# MTB-v2_0_0.net
KiCad netlist of a schematic drawn in EAGLE
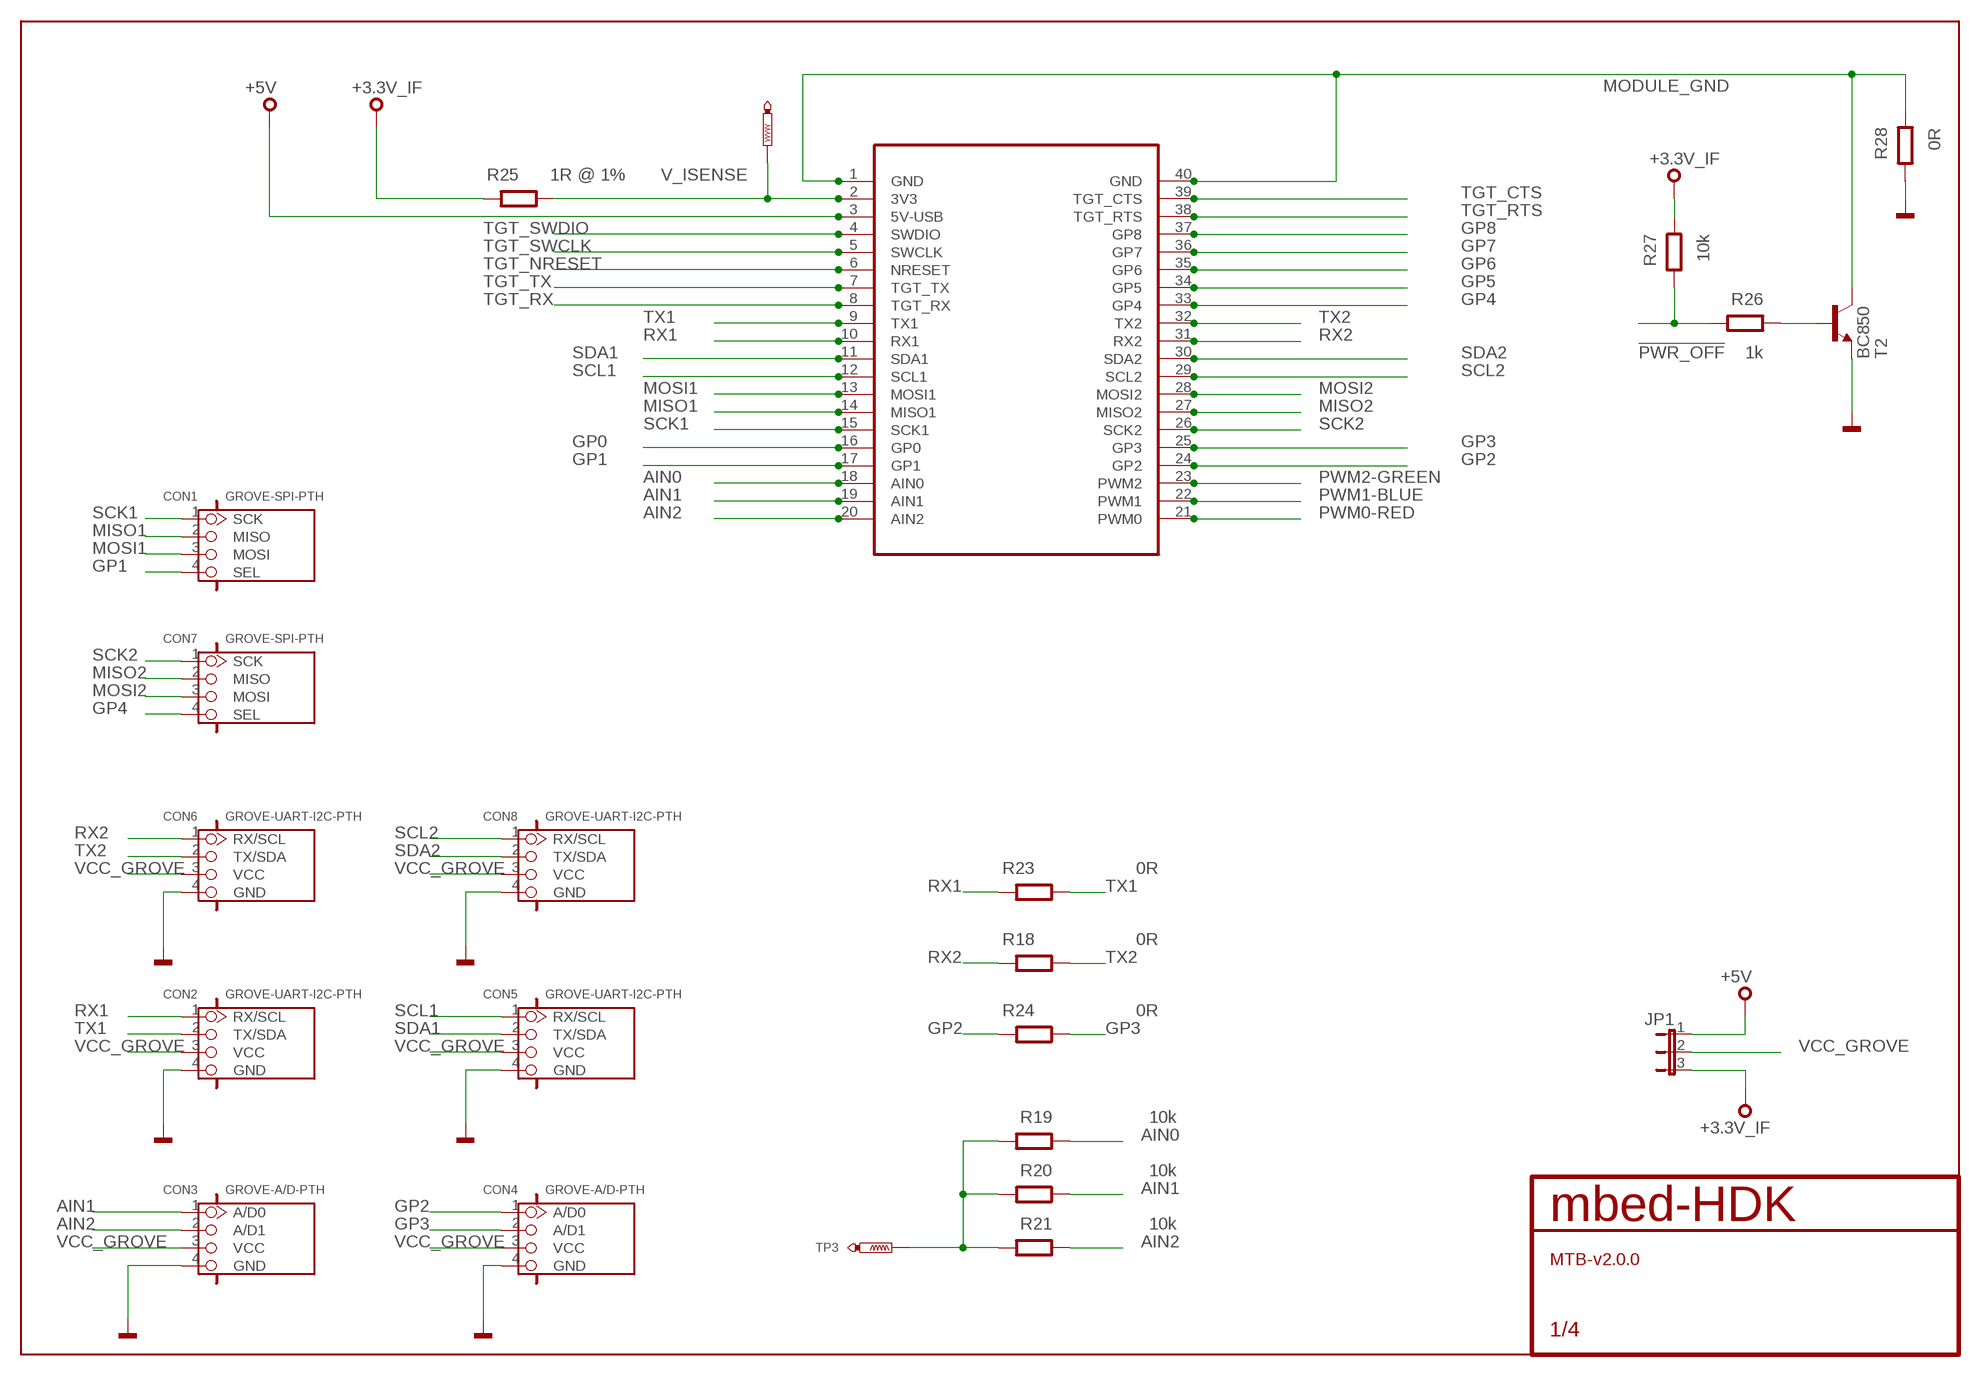
[diagram p0: schematic, sheet 1]
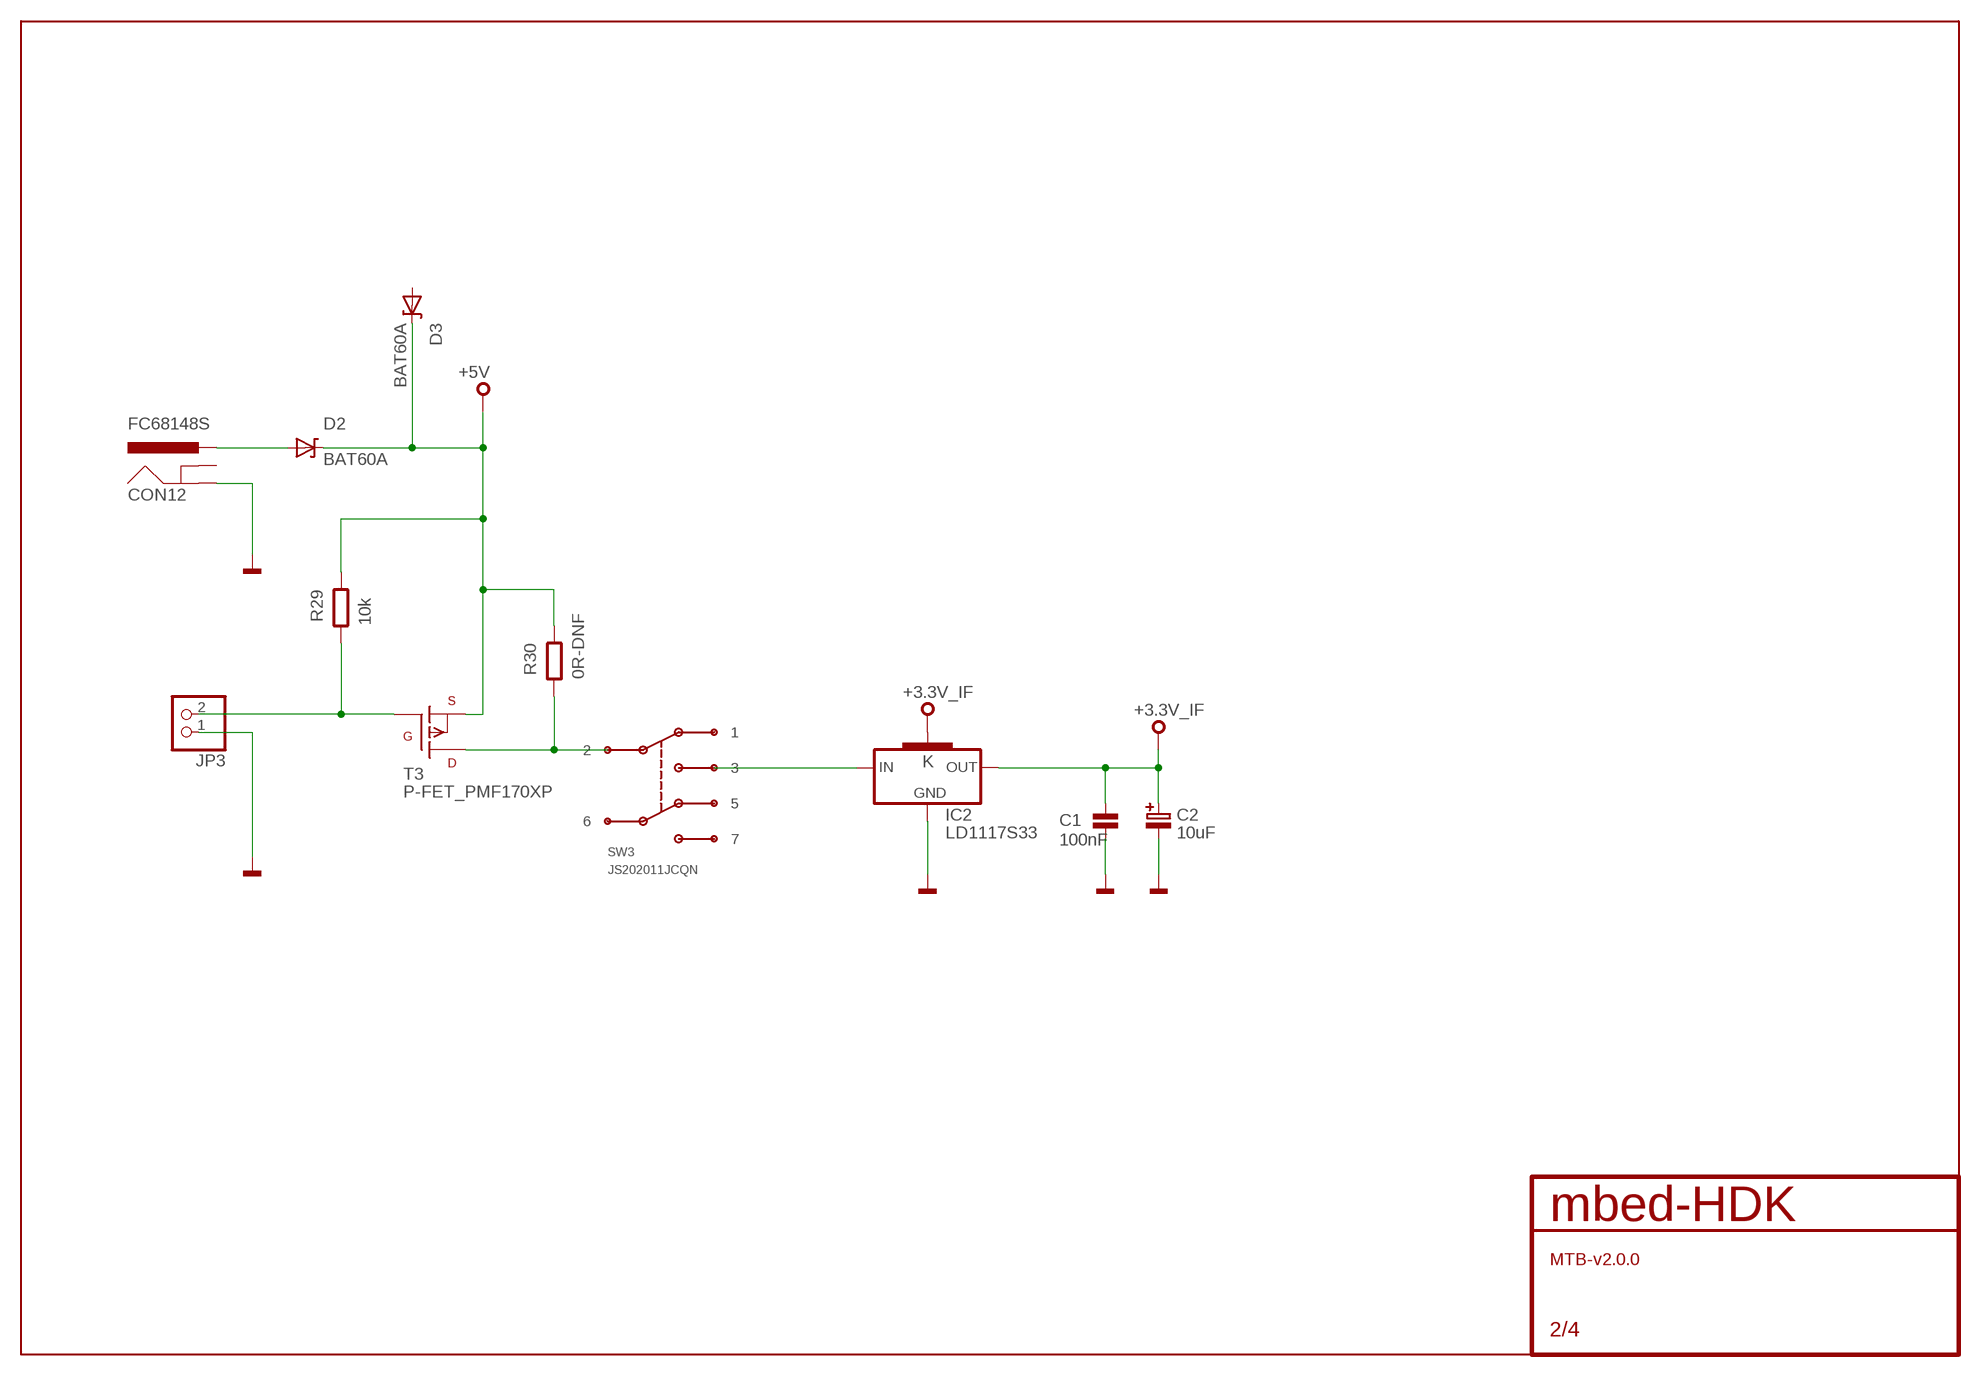
[diagram p1: schematic, sheet 2]
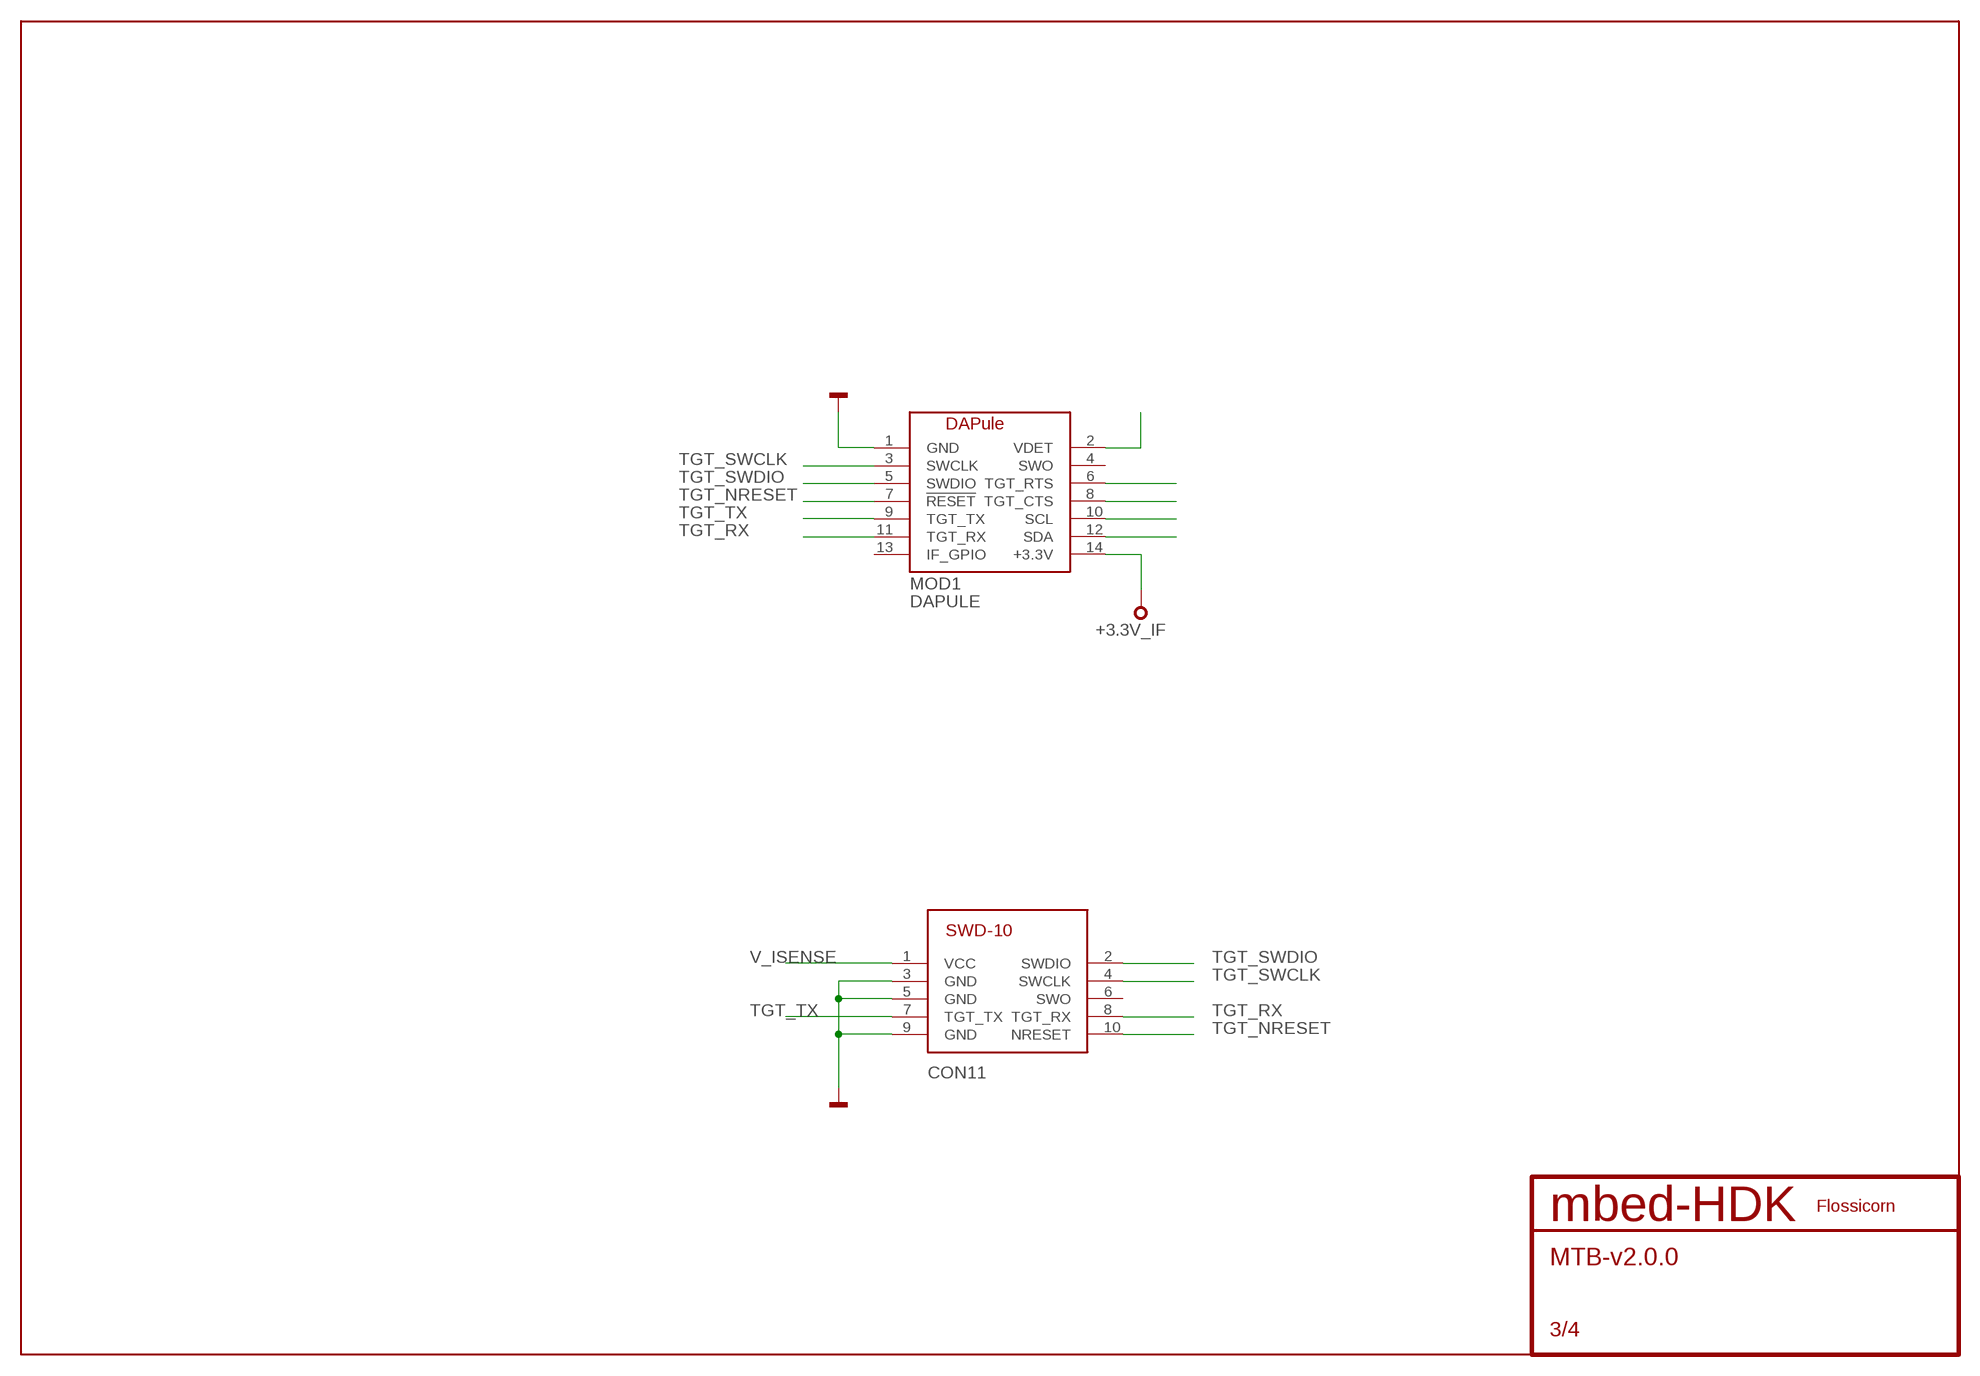
[diagram p2: schematic, sheet 3]
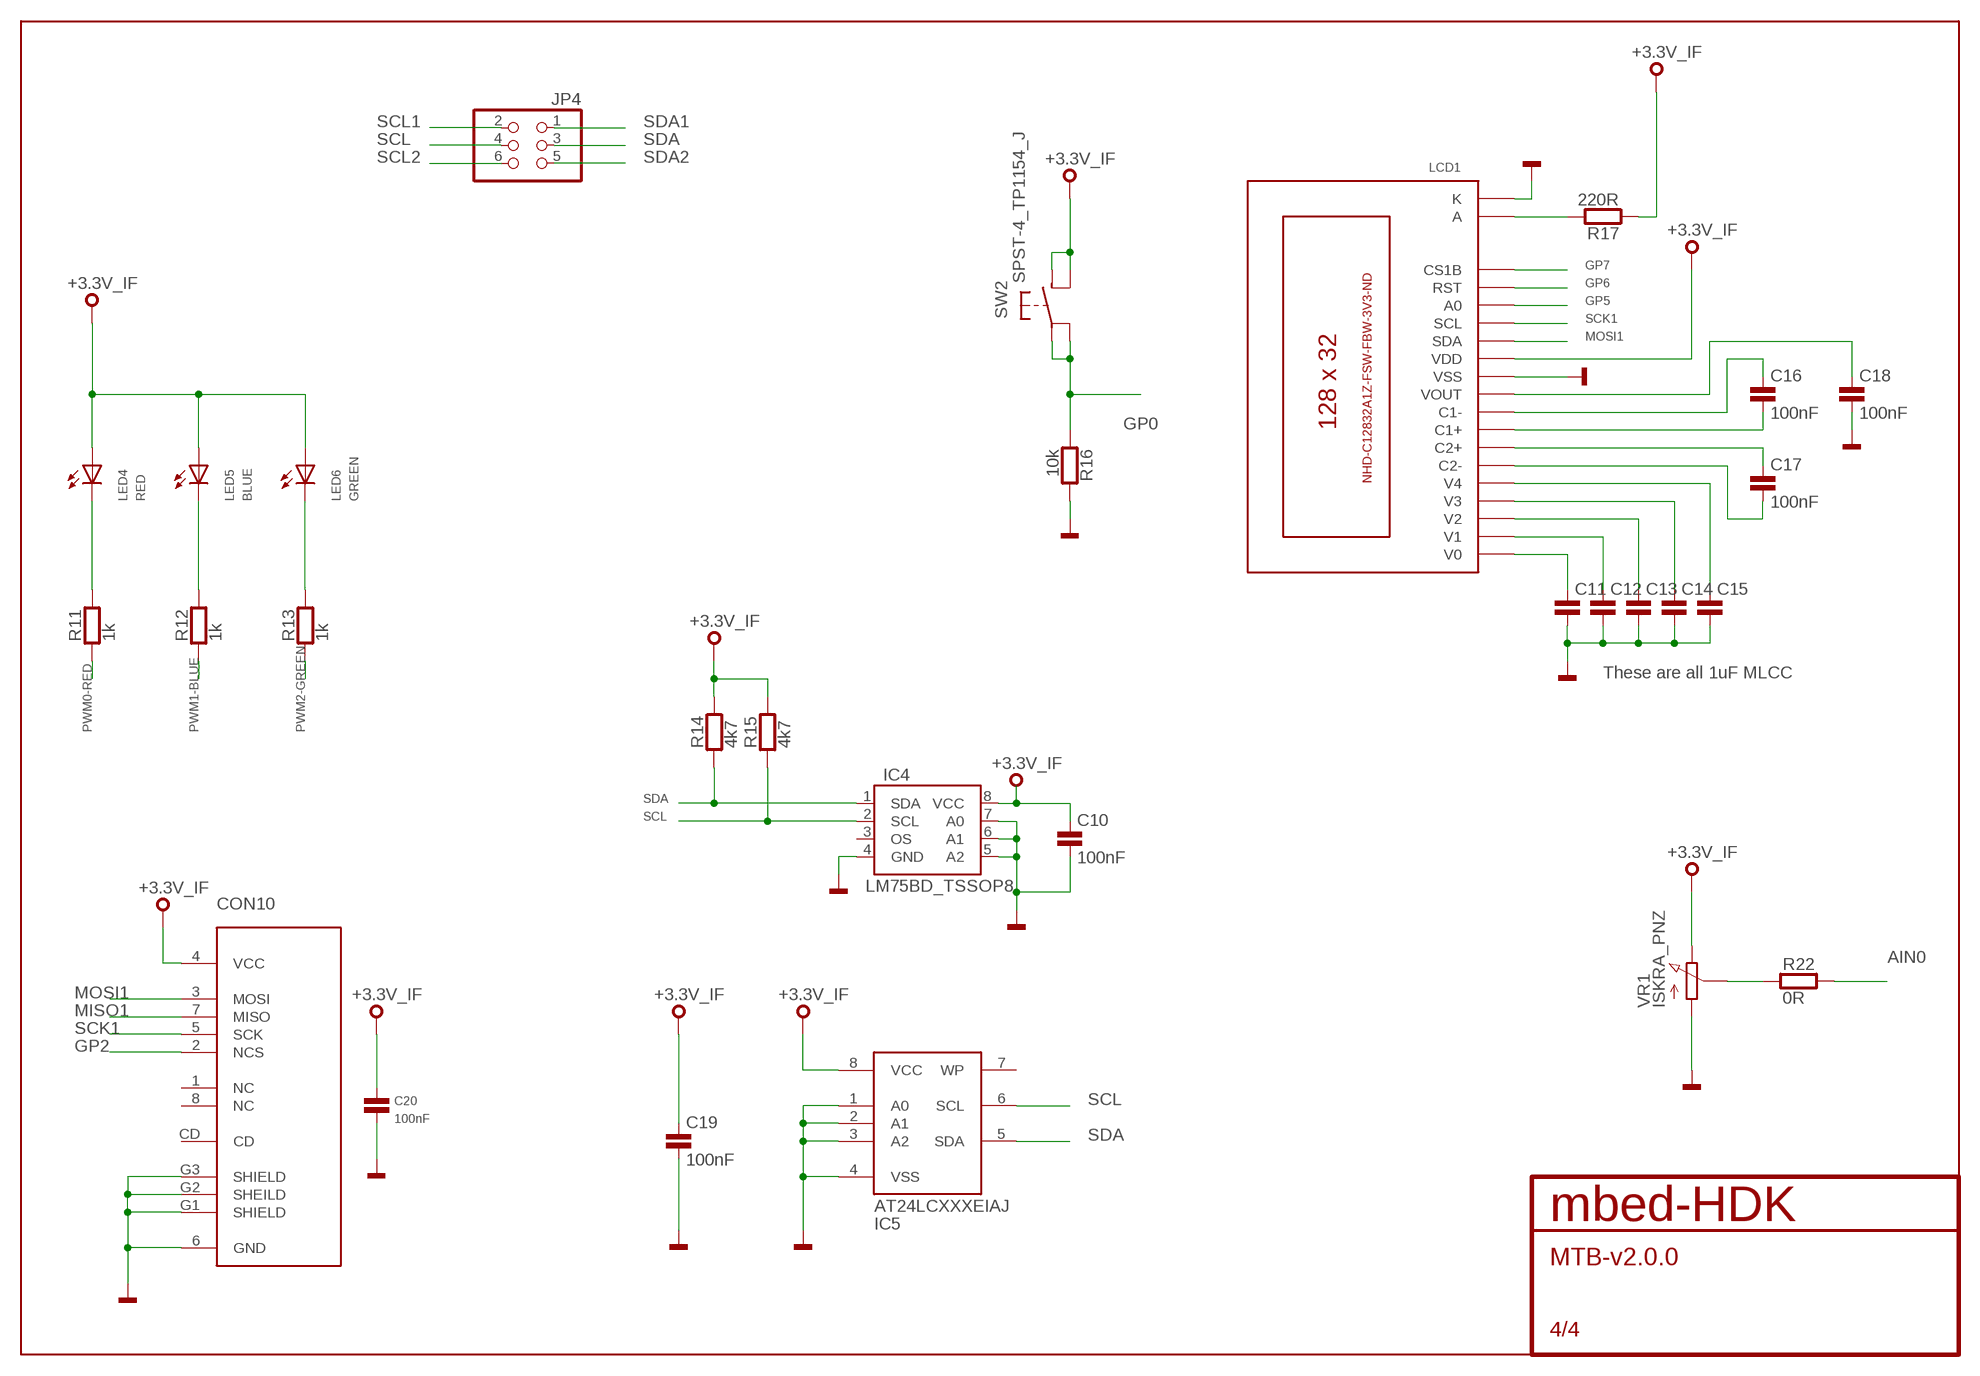
[diagram p3: schematic, sheet 4]

(export (version "E")
  (design (tool "Eeschema 10.0.6"))
  (components
    (comp (ref "CON1")
      (value "GROVE-SPI-PTH")
      (footprint "eagle-import:HW4-2.0")
      (libsource (lib "eagle-import") (part "GROVE-SPI-PTH"))
    )
    (comp (ref "CON2")
      (value "GROVE-UART-I2C-PTH")
      (footprint "eagle-import:HW4-2.0")
      (libsource (lib "eagle-import") (part "GROVE-UART-I2C-PTH"))
    )
    (comp (ref "CON3")
      (value "GROVE-A/D-PTH")
      (footprint "eagle-import:HW4-2.0")
      (libsource (lib "eagle-import") (part "GROVE-A/D-PTH"))
    )
    (comp (ref "CON4")
      (value "GROVE-A/D-PTH")
      (footprint "eagle-import:HW4-2.0")
      (libsource (lib "eagle-import") (part "GROVE-A/D-PTH"))
    )
    (comp (ref "CON5")
      (value "GROVE-UART-I2C-PTH")
      (footprint "eagle-import:HW4-2.0")
      (libsource (lib "eagle-import") (part "GROVE-UART-I2C-PTH"))
    )
    (comp (ref "CON6")
      (value "GROVE-UART-I2C-PTH")
      (footprint "eagle-import:HW4-2.0")
      (libsource (lib "eagle-import") (part "GROVE-UART-I2C-PTH"))
    )
    (comp (ref "CON7")
      (value "GROVE-SPI-PTH")
      (footprint "eagle-import:HW4-2.0")
      (libsource (lib "eagle-import") (part "GROVE-SPI-PTH"))
    )
    (comp (ref "CON8")
      (value "GROVE-UART-I2C-PTH")
      (footprint "eagle-import:HW4-2.0")
      (libsource (lib "eagle-import") (part "GROVE-UART-I2C-PTH"))
    )
    (comp (ref "JP1")
      (value "JP2E")
      (footprint "eagle-import:JP2")
      (libsource (lib "eagle-import") (part "JP2E"))
    )
    (comp (ref "R18")
      (value "0R")
      (footprint "eagle-import:0603@1")
      (libsource (lib "eagle-import") (part "R0603"))
    )
    (comp (ref "R19")
      (value "10k")
      (footprint "eagle-import:0603@1")
      (libsource (lib "eagle-import") (part "R0603"))
    )
    (comp (ref "R20")
      (value "10k")
      (footprint "eagle-import:0603@1")
      (libsource (lib "eagle-import") (part "R0603"))
    )
    (comp (ref "R21")
      (value "10k")
      (footprint "eagle-import:0603@1")
      (libsource (lib "eagle-import") (part "R0603"))
    )
    (comp (ref "R23")
      (value "0R")
      (footprint "eagle-import:0603@1")
      (libsource (lib "eagle-import") (part "R0603"))
    )
    (comp (ref "R24")
      (value "0R")
      (footprint "eagle-import:0603@1")
      (libsource (lib "eagle-import") (part "R0603"))
    )
    (comp (ref "R25")
      (value "1R @ 1%")
      (footprint "eagle-import:0603@1")
      (libsource (lib "eagle-import") (part "R0603"))
    )
    (comp (ref "R26")
      (value "1k")
      (footprint "eagle-import:0603@1")
      (libsource (lib "eagle-import") (part "R0603"))
    )
    (comp (ref "R27")
      (value "10k")
      (footprint "eagle-import:0603@1")
      (libsource (lib "eagle-import") (part "R0603"))
    )
    (comp (ref "R28")
      (value "0R")
      (footprint "eagle-import:0603@1")
      (libsource (lib "eagle-import") (part "R0603"))
    )
    (comp (ref "SKT1")
      (value "MODULE_SOCKET")
      (footprint "eagle-import:MODULE_SOCKET")
      (libsource (lib "eagle-import") (part "MODULE_SOCKET"))
    )
    (comp (ref "T2")
      (value "BC850")
      (footprint "eagle-import:SOT23")
      (libsource (lib "eagle-import") (part "BC850"))
    )
    (comp (ref "TP3")
      (value "TEST-POINT-50R-PTH")
      (footprint "eagle-import:TP50-PTH")
      (libsource (lib "eagle-import") (part "TEST-POINT-50R-PTH"))
    )
    (comp (ref "TP8")
      (value "PTR1TP07R")
      (footprint "eagle-import:TP07R")
      (libsource (lib "eagle-import") (part "PTR1TP07R"))
    )
    (comp (ref "CON11")
      (value "SWD-10/TC2050_SMD")
      (footprint "eagle-import:FTSH-105-02")
      (libsource (lib "eagle-import") (part "SWD-10/TC2050_SMD"))
    )
    (comp (ref "MOD1")
      (value "DAPULE")
      (footprint "eagle-import:DAPULE")
      (libsource (lib "eagle-import") (part "DAPULE"))
    )
    (comp (ref "SS1")
      (value "FLOSSICORN0.5")
      (footprint "eagle-import:FLOSSICORN-0.5")
      (libsource (lib "eagle-import") (part "FLOSSICORN0.5"))
    )
    (comp (ref "C10")
      (value "100nF")
      (footprint "eagle-import:0603")
      (libsource (lib "eagle-import") (part "mbed-rlcq_C0603"))
    )
    (comp (ref "C11")
      (value "100nF")
      (footprint "eagle-import:0603")
      (libsource (lib "eagle-import") (part "mbed-rlcq_C0603"))
    )
    (comp (ref "C12")
      (value "100nF")
      (footprint "eagle-import:0603")
      (libsource (lib "eagle-import") (part "mbed-rlcq_C0603"))
    )
    (comp (ref "C13")
      (value "100nF")
      (footprint "eagle-import:0603")
      (libsource (lib "eagle-import") (part "mbed-rlcq_C0603"))
    )
    (comp (ref "C14")
      (value "100nF")
      (footprint "eagle-import:0603")
      (libsource (lib "eagle-import") (part "mbed-rlcq_C0603"))
    )
    (comp (ref "C15")
      (value "100nF")
      (footprint "eagle-import:0603")
      (libsource (lib "eagle-import") (part "mbed-rlcq_C0603"))
    )
    (comp (ref "C16")
      (value "100nF")
      (footprint "eagle-import:0603")
      (libsource (lib "eagle-import") (part "mbed-rlcq_C0603"))
    )
    (comp (ref "C17")
      (value "100nF")
      (footprint "eagle-import:0603")
      (libsource (lib "eagle-import") (part "mbed-rlcq_C0603"))
    )
    (comp (ref "C18")
      (value "100nF")
      (footprint "eagle-import:0603")
      (libsource (lib "eagle-import") (part "mbed-rlcq_C0603"))
    )
    (comp (ref "C19")
      (value "100nF")
      (footprint "eagle-import:0603")
      (libsource (lib "eagle-import") (part "mbed-rlcq_C0603"))
    )
    (comp (ref "C20")
      (value "100nF")
      (footprint "eagle-import:0603")
      (libsource (lib "eagle-import") (part "C0603"))
    )
    (comp (ref "CON10")
      (value "MICRO-SD")
      (footprint "eagle-import:AMPHENOL-101-00660-68-6")
      (libsource (lib "eagle-import") (part "MICRO-SD"))
    )
    (comp (ref "IC4")
      (value "LM75BD_TSSOP8")
      (footprint "eagle-import:TSSOP8")
      (libsource (lib "eagle-import") (part "LM75BD_TSSOP8"))
    )
    (comp (ref "IC5")
      (value "AT24LCXXXEIAJ")
      (footprint "eagle-import:SO08-EIAJ")
      (libsource (lib "eagle-import") (part "AT24LCXXXEIAJ"))
    )
    (comp (ref "JP4")
      (value "PINHD-2X3")
      (footprint "eagle-import:2X03")
      (libsource (lib "eagle-import") (part "PINHD-2X3"))
    )
    (comp (ref "LCD1")
      (value "C12832A1Z")
      (footprint "eagle-import:C12832A1Z")
      (libsource (lib "eagle-import") (part "C12832A1Z"))
    )
    (comp (ref "LED4")
      (value "RED")
      (footprint "eagle-import:CHIPLED_0603")
      (libsource (lib "eagle-import") (part "LED0603"))
    )
    (comp (ref "LED5")
      (value "BLUE")
      (footprint "eagle-import:CHIPLED_0603")
      (libsource (lib "eagle-import") (part "LED0603"))
    )
    (comp (ref "LED6")
      (value "GREEN")
      (footprint "eagle-import:CHIPLED_0603")
      (libsource (lib "eagle-import") (part "LED0603"))
    )
    (comp (ref "R11")
      (value "1k")
      (footprint "eagle-import:0603")
      (libsource (lib "eagle-import") (part "mbed-rlcq_R0603"))
    )
    (comp (ref "R12")
      (value "1k")
      (footprint "eagle-import:0603")
      (libsource (lib "eagle-import") (part "mbed-rlcq_R0603"))
    )
    (comp (ref "R13")
      (value "1k")
      (footprint "eagle-import:0603")
      (libsource (lib "eagle-import") (part "mbed-rlcq_R0603"))
    )
    (comp (ref "R14")
      (value "4k7")
      (footprint "eagle-import:0603")
      (libsource (lib "eagle-import") (part "mbed-rlcq_R0603"))
    )
    (comp (ref "R15")
      (value "4k7")
      (footprint "eagle-import:0603")
      (libsource (lib "eagle-import") (part "mbed-rlcq_R0603"))
    )
    (comp (ref "R16")
      (value "10k")
      (footprint "eagle-import:0603")
      (libsource (lib "eagle-import") (part "mbed-rlcq_R0603"))
    )
    (comp (ref "R17")
      (value "220R")
      (footprint "eagle-import:0603")
      (libsource (lib "eagle-import") (part "mbed-rlcq_R0603"))
    )
    (comp (ref "R22")
      (value "0R")
      (footprint "eagle-import:0603")
      (libsource (lib "eagle-import") (part "mbed-rlcq_R0603"))
    )
    (comp (ref "SW2")
      (value "SPST-4_TP1154_J")
      (footprint "eagle-import:TP-1154X")
      (libsource (lib "eagle-import") (part "SPST-4_TP1154_J"))
    )
    (comp (ref "VR1")
      (value "ISKRA_PNZ")
      (footprint "eagle-import:CA14V")
      (libsource (lib "eagle-import") (part "ISKRA_PNZ"))
    )
    (comp (ref "C1")
      (value "100nF")
      (footprint "eagle-import:0603")
      (libsource (lib "eagle-import") (part "C0603"))
    )
    (comp (ref "C2")
      (value "10uF")
      (footprint "eagle-import:SMC_B")
      (libsource (lib "eagle-import") (part "C-POLB"))
    )
    (comp (ref "CON12")
      (value "FC68148S")
      (footprint "eagle-import:FC68148S")
      (libsource (lib "eagle-import") (part "FC68148S"))
    )
    (comp (ref "D2")
      (value "BAT60A")
      (footprint "eagle-import:SOD323")
      (fields (field (name "MF") "Infineon"))
      (libsource (lib "eagle-import") (part "BAT60A"))
    )
    (comp (ref "D3")
      (value "BAT60A")
      (footprint "eagle-import:SOD323")
      (fields (field (name "MF") "Infineon"))
      (libsource (lib "eagle-import") (part "BAT60A"))
    )
    (comp (ref "IC2")
      (value "LD1117S33")
      (footprint "eagle-import:SOT223")
      (libsource (lib "eagle-import") (part "LD1117S33"))
    )
    (comp (ref "JP3")
      (value "PINHD-1X2")
      (footprint "eagle-import:1X02")
      (libsource (lib "eagle-import") (part "PINHD-1X2"))
    )
    (comp (ref "R29")
      (value "10k")
      (footprint "eagle-import:0603@1")
      (libsource (lib "eagle-import") (part "R0603"))
    )
    (comp (ref "R30")
      (value "0R-DNF")
      (footprint "eagle-import:0603@1")
      (libsource (lib "eagle-import") (part "R0603"))
    )
    (comp (ref "SW3")
      (value "JS202011JCQN")
      (footprint "eagle-import:JS202011JCQN")
      (fields (field (name "MF") "C&K Components"))
      (libsource (lib "eagle-import") (part "JS202011JCQN"))
    )
    (comp (ref "T3")
      (value "P-FET_PMF170XP")
      (footprint "eagle-import:SOT23-BEC")
      (libsource (lib "eagle-import") (part "P-FET_PMF170XP"))
    )
  )
  (nets
    (net (code "1") (name "+3.3V_IF") (class "Default")
      (node (ref "C1") (pin "1") (pinfunction "P$1_1") (pintype "passive"))
      (node (ref "C10") (pin "1") (pinfunction "P$1_1") (pintype "passive"))
      (node (ref "C19") (pin "1") (pinfunction "P$1_1") (pintype "passive"))
      (node (ref "C2") (pin "+") (pinfunction "+_+") (pintype "passive"))
      (node (ref "C20") (pin "1") (pinfunction "P$1_1") (pintype "passive"))
      (node (ref "CON10") (pin "4") (pinfunction "VCC_4") (pintype "bidirectional"))
      (node (ref "IC2") (pin "2") (pinfunction "OUT_2") (pintype "passive"))
      (node (ref "IC2") (pin "4") (pinfunction "K_4") (pintype "passive"))
      (node (ref "IC4") (pin "8") (pinfunction "VCC_8") (pintype "bidirectional"))
      (node (ref "IC5") (pin "8") (pinfunction "VCC_8") (pintype "power_in"))
      (node (ref "JP1") (pin "3") (pinfunction "3_3") (pintype "passive"))
      (node (ref "LCD1") (pin "P$12") (pinfunction "VDD_P$12") (pintype "bidirectional"))
      (node (ref "LED4") (pin "A") (pinfunction "A_A") (pintype "passive"))
      (node (ref "LED5") (pin "A") (pinfunction "A_A") (pintype "passive"))
      (node (ref "LED6") (pin "A") (pinfunction "A_A") (pintype "passive"))
      (node (ref "MOD1") (pin "14") (pinfunction "+3.3V_14") (pintype "bidirectional"))
      (node (ref "R14") (pin "2") (pinfunction "P$2_2") (pintype "passive"))
      (node (ref "R15") (pin "2") (pinfunction "P$2_2") (pintype "passive"))
      (node (ref "R17") (pin "1") (pinfunction "P$1_1") (pintype "passive"))
      (node (ref "R25") (pin "2") (pinfunction "P$2_2") (pintype "passive"))
      (node (ref "R27") (pin "1") (pinfunction "P$1_1") (pintype "passive"))
      (node (ref "SW2") (pin "B1") (pinfunction "B1_B1") (pintype "passive"))
      (node (ref "SW2") (pin "B2") (pinfunction "B2_B2") (pintype "passive"))
      (node (ref "VR1") (pin "P$3") (pinfunction "E_P$3") (pintype "passive"))
    )
    (net (code "2") (name "+5V") (class "Default")
      (node (ref "D2") (pin "K") (pinfunction "K_K") (pintype "passive"))
      (node (ref "D3") (pin "K") (pinfunction "K_K") (pintype "passive"))
      (node (ref "JP1") (pin "1") (pinfunction "1_1") (pintype "passive"))
      (node (ref "R29") (pin "1") (pinfunction "P$1_1") (pintype "passive"))
      (node (ref "R30") (pin "1") (pinfunction "P$1_1") (pintype "passive"))
      (node (ref "SKT1") (pin "3") (pinfunction "5V-USB_3") (pintype "bidirectional"))
      (node (ref "SKT1") (pin "P$43") (pinfunction "P$43_P$43") (pintype "bidirectional"))
      (node (ref "T3") (pin "E") (pinfunction "S_E") (pintype "passive"))
    )
    (net (code "3") (name "AIN0") (class "Default")
      (node (ref "R19") (pin "1") (pinfunction "P$1_1") (pintype "passive"))
      (node (ref "R22") (pin "2") (pinfunction "P$2_2") (pintype "passive"))
      (node (ref "SKT1") (pin "18") (pinfunction "AIN0_18") (pintype "bidirectional"))
      (node (ref "SKT1") (pin "P$58") (pinfunction "P$58_P$58") (pintype "bidirectional"))
    )
    (net (code "4") (name "AIN1") (class "Default")
      (node (ref "CON3") (pin "1") (pinfunction "A/D0_1") (pintype "bidirectional"))
      (node (ref "R20") (pin "1") (pinfunction "P$1_1") (pintype "passive"))
      (node (ref "SKT1") (pin "19") (pinfunction "AIN1_19") (pintype "bidirectional"))
      (node (ref "SKT1") (pin "P$59") (pinfunction "P$59_P$59") (pintype "bidirectional"))
    )
    (net (code "5") (name "AIN2") (class "Default")
      (node (ref "CON3") (pin "2") (pinfunction "A/D1_2") (pintype "bidirectional"))
      (node (ref "R21") (pin "1") (pinfunction "P$1_1") (pintype "passive"))
      (node (ref "SKT1") (pin "20") (pinfunction "AIN2_20") (pintype "bidirectional"))
      (node (ref "SKT1") (pin "P$60") (pinfunction "P$60_P$60") (pintype "bidirectional"))
    )
    (net (code "6") (name "GND") (class "Default")
      (node (ref "C1") (pin "2") (pinfunction "P$2_2") (pintype "passive"))
      (node (ref "C10") (pin "2") (pinfunction "P$2_2") (pintype "passive"))
      (node (ref "C11") (pin "2") (pinfunction "P$2_2") (pintype "passive"))
      (node (ref "C12") (pin "2") (pinfunction "P$2_2") (pintype "passive"))
      (node (ref "C13") (pin "2") (pinfunction "P$2_2") (pintype "passive"))
      (node (ref "C14") (pin "2") (pinfunction "P$2_2") (pintype "passive"))
      (node (ref "C15") (pin "2") (pinfunction "P$2_2") (pintype "passive"))
      (node (ref "C18") (pin "2") (pinfunction "P$2_2") (pintype "passive"))
      (node (ref "C19") (pin "2") (pinfunction "P$2_2") (pintype "passive"))
      (node (ref "C2") (pin "-") (pinfunction "-_-") (pintype "passive"))
      (node (ref "C20") (pin "2") (pinfunction "P$2_2") (pintype "passive"))
      (node (ref "CON10") (pin "6") (pinfunction "GND_6") (pintype "bidirectional"))
      (node (ref "CON10") (pin "G1") (pinfunction "SHIELD_G1") (pintype "bidirectional"))
      (node (ref "CON10") (pin "G2") (pinfunction "SHEILD_G2") (pintype "bidirectional"))
      (node (ref "CON10") (pin "G3") (pinfunction "SHIELD_G3") (pintype "bidirectional"))
      (node (ref "CON11") (pin "3") (pinfunction "GND_3") (pintype "bidirectional"))
      (node (ref "CON11") (pin "5") (pinfunction "GND_5") (pintype "bidirectional"))
      (node (ref "CON11") (pin "9") (pinfunction "GND_9") (pintype "bidirectional"))
      (node (ref "CON12") (pin "3") (pinfunction "GND_3") (pintype "bidirectional"))
      (node (ref "CON2") (pin "4") (pinfunction "GND_4") (pintype "bidirectional"))
      (node (ref "CON3") (pin "4") (pinfunction "GND_4") (pintype "bidirectional"))
      (node (ref "CON4") (pin "4") (pinfunction "GND_4") (pintype "bidirectional"))
      (node (ref "CON5") (pin "4") (pinfunction "GND_4") (pintype "bidirectional"))
      (node (ref "CON6") (pin "4") (pinfunction "GND_4") (pintype "bidirectional"))
      (node (ref "CON8") (pin "4") (pinfunction "GND_4") (pintype "bidirectional"))
      (node (ref "IC2") (pin "1") (pinfunction "GND_1") (pintype "input"))
      (node (ref "IC4") (pin "4") (pinfunction "GND_4") (pintype "bidirectional"))
      (node (ref "IC4") (pin "5") (pinfunction "A2_5") (pintype "bidirectional"))
      (node (ref "IC4") (pin "6") (pinfunction "A1_6") (pintype "bidirectional"))
      (node (ref "IC4") (pin "7") (pinfunction "A0_7") (pintype "bidirectional"))
      (node (ref "IC5") (pin "1") (pinfunction "A0_1") (pintype "bidirectional"))
      (node (ref "IC5") (pin "2") (pinfunction "A1_2") (pintype "bidirectional"))
      (node (ref "IC5") (pin "3") (pinfunction "A2_3") (pintype "bidirectional"))
      (node (ref "IC5") (pin "4") (pinfunction "VSS_4") (pintype "power_in"))
      (node (ref "JP3") (pin "1") (pinfunction "1_1") (pintype "passive"))
      (node (ref "LCD1") (pin "K") (pinfunction "K_K") (pintype "bidirectional"))
      (node (ref "LCD1") (pin "P$11") (pinfunction "VSS_P$11") (pintype "bidirectional"))
      (node (ref "MOD1") (pin "1") (pinfunction "GND_1") (pintype "bidirectional"))
      (node (ref "R16") (pin "2") (pinfunction "P$2_2") (pintype "passive"))
      (node (ref "R28") (pin "2") (pinfunction "P$2_2") (pintype "passive"))
      (node (ref "T2") (pin "2") (pinfunction "E_2") (pintype "passive"))
      (node (ref "VR1") (pin "P$1") (pinfunction "A_P$1") (pintype "passive"))
    )
    (net (code "7") (name "GP0") (class "Default")
      (node (ref "R16") (pin "1") (pinfunction "P$1_1") (pintype "passive"))
      (node (ref "SKT1") (pin "16") (pinfunction "GP0_16") (pintype "bidirectional"))
      (node (ref "SKT1") (pin "P$56") (pinfunction "P$56_P$56") (pintype "bidirectional"))
      (node (ref "SW2") (pin "A1") (pinfunction "A1_A1") (pintype "passive"))
      (node (ref "SW2") (pin "A2") (pinfunction "A2_A2") (pintype "passive"))
    )
    (net (code "8") (name "GP1") (class "Default")
      (node (ref "CON1") (pin "4") (pinfunction "SEL_4") (pintype "bidirectional"))
      (node (ref "SKT1") (pin "17") (pinfunction "GP1_17") (pintype "bidirectional"))
      (node (ref "SKT1") (pin "P$57") (pinfunction "P$57_P$57") (pintype "bidirectional"))
    )
    (net (code "9") (name "GP2") (class "Default")
      (node (ref "CON10") (pin "2") (pinfunction "NCS_2") (pintype "bidirectional"))
      (node (ref "CON4") (pin "1") (pinfunction "A/D0_1") (pintype "bidirectional"))
      (node (ref "R24") (pin "2") (pinfunction "P$2_2") (pintype "passive"))
      (node (ref "SKT1") (pin "24") (pinfunction "GP2_24") (pintype "bidirectional"))
      (node (ref "SKT1") (pin "P$64") (pinfunction "P$64_P$64") (pintype "bidirectional"))
    )
    (net (code "10") (name "GP3") (class "Default")
      (node (ref "CON4") (pin "2") (pinfunction "A/D1_2") (pintype "bidirectional"))
      (node (ref "R24") (pin "1") (pinfunction "P$1_1") (pintype "passive"))
      (node (ref "SKT1") (pin "25") (pinfunction "GP3_25") (pintype "bidirectional"))
      (node (ref "SKT1") (pin "P$65") (pinfunction "P$65_P$65") (pintype "bidirectional"))
    )
    (net (code "11") (name "GP4") (class "Default")
      (node (ref "CON7") (pin "4") (pinfunction "SEL_4") (pintype "bidirectional"))
      (node (ref "SKT1") (pin "33") (pinfunction "GP4_33") (pintype "bidirectional"))
      (node (ref "SKT1") (pin "P$73") (pinfunction "P$73_P$73") (pintype "bidirectional"))
    )
    (net (code "12") (name "GP5") (class "Default")
      (node (ref "LCD1") (pin "P$15") (pinfunction "A0_P$15") (pintype "bidirectional"))
      (node (ref "SKT1") (pin "34") (pinfunction "GP5_34") (pintype "bidirectional"))
      (node (ref "SKT1") (pin "P$74") (pinfunction "P$74_P$74") (pintype "bidirectional"))
    )
    (net (code "13") (name "GP6") (class "Default")
      (node (ref "LCD1") (pin "P$16") (pinfunction "RST_P$16") (pintype "bidirectional"))
      (node (ref "SKT1") (pin "35") (pinfunction "GP6_35") (pintype "bidirectional"))
      (node (ref "SKT1") (pin "P$75") (pinfunction "P$75_P$75") (pintype "bidirectional"))
    )
    (net (code "14") (name "GP7") (class "Default")
      (node (ref "LCD1") (pin "P$17") (pinfunction "CS1B_P$17") (pintype "bidirectional"))
      (node (ref "SKT1") (pin "36") (pinfunction "GP7_36") (pintype "bidirectional"))
      (node (ref "SKT1") (pin "P$76") (pinfunction "P$76_P$76") (pintype "bidirectional"))
    )
    (net (code "15") (name "GP8") (class "Default")
      (node (ref "SKT1") (pin "37") (pinfunction "GP8_37") (pintype "bidirectional"))
      (node (ref "SKT1") (pin "P$77") (pinfunction "P$77_P$77") (pintype "bidirectional"))
    )
    (net (code "16") (name "MISO1") (class "Default")
      (node (ref "CON1") (pin "2") (pinfunction "MISO_2") (pintype "bidirectional"))
      (node (ref "CON10") (pin "7") (pinfunction "MISO_7") (pintype "bidirectional"))
      (node (ref "SKT1") (pin "14") (pinfunction "MISO1_14") (pintype "bidirectional"))
      (node (ref "SKT1") (pin "P$54") (pinfunction "P$54_P$54") (pintype "bidirectional"))
    )
    (net (code "17") (name "MISO2") (class "Default")
      (node (ref "CON7") (pin "2") (pinfunction "MISO_2") (pintype "bidirectional"))
      (node (ref "SKT1") (pin "27") (pinfunction "MISO2_27") (pintype "bidirectional"))
      (node (ref "SKT1") (pin "P$67") (pinfunction "P$67_P$67") (pintype "bidirectional"))
    )
    (net (code "18") (name "MODULE_GND") (class "Default")
      (node (ref "R28") (pin "1") (pinfunction "P$1_1") (pintype "passive"))
      (node (ref "SKT1") (pin "1") (pinfunction "GND_1") (pintype "bidirectional"))
      (node (ref "SKT1") (pin "40") (pinfunction "GND_40") (pintype "bidirectional"))
      (node (ref "SKT1") (pin "P$41") (pinfunction "P$41_P$41") (pintype "bidirectional"))
      (node (ref "SKT1") (pin "P$80") (pinfunction "P$80_P$80") (pintype "bidirectional"))
      (node (ref "T2") (pin "3") (pinfunction "C_3") (pintype "passive"))
    )
    (net (code "19") (name "MOSI1") (class "Default")
      (node (ref "CON1") (pin "3") (pinfunction "MOSI_3") (pintype "bidirectional"))
      (node (ref "CON10") (pin "3") (pinfunction "MOSI_3") (pintype "bidirectional"))
      (node (ref "LCD1") (pin "P$13") (pinfunction "SDA_P$13") (pintype "bidirectional"))
      (node (ref "SKT1") (pin "13") (pinfunction "MOSI1_13") (pintype "bidirectional"))
      (node (ref "SKT1") (pin "P$53") (pinfunction "P$53_P$53") (pintype "bidirectional"))
    )
    (net (code "20") (name "MOSI2") (class "Default")
      (node (ref "CON7") (pin "3") (pinfunction "MOSI_3") (pintype "bidirectional"))
      (node (ref "SKT1") (pin "28") (pinfunction "MOSI2_28") (pintype "bidirectional"))
      (node (ref "SKT1") (pin "P$68") (pinfunction "P$68_P$68") (pintype "bidirectional"))
    )
    (net (code "21") (name "Net-(C11-P$1)") (class "Default")
      (node (ref "C11") (pin "1") (pinfunction "P$1_1") (pintype "passive"))
      (node (ref "LCD1") (pin "P$1") (pinfunction "V0_P$1") (pintype "bidirectional"))
    )
    (net (code "22") (name "Net-(C12-P$1)") (class "Default")
      (node (ref "C12") (pin "1") (pinfunction "P$1_1") (pintype "passive"))
      (node (ref "LCD1") (pin "P$2") (pinfunction "V1_P$2") (pintype "bidirectional"))
    )
    (net (code "23") (name "Net-(C13-P$1)") (class "Default")
      (node (ref "C13") (pin "1") (pinfunction "P$1_1") (pintype "passive"))
      (node (ref "LCD1") (pin "P$3") (pinfunction "V2_P$3") (pintype "bidirectional"))
    )
    (net (code "24") (name "Net-(C14-P$1)") (class "Default")
      (node (ref "C14") (pin "1") (pinfunction "P$1_1") (pintype "passive"))
      (node (ref "LCD1") (pin "P$4") (pinfunction "V3_P$4") (pintype "bidirectional"))
    )
    (net (code "25") (name "Net-(C15-P$1)") (class "Default")
      (node (ref "C15") (pin "1") (pinfunction "P$1_1") (pintype "passive"))
      (node (ref "LCD1") (pin "P$5") (pinfunction "V4_P$5") (pintype "bidirectional"))
    )
    (net (code "26") (name "Net-(C16-P$1)") (class "Default")
      (node (ref "C16") (pin "1") (pinfunction "P$1_1") (pintype "passive"))
      (node (ref "LCD1") (pin "P$9") (pinfunction "C1-_P$9") (pintype "bidirectional"))
    )
    (net (code "27") (name "Net-(C16-P$2)") (class "Default")
      (node (ref "C16") (pin "2") (pinfunction "P$2_2") (pintype "passive"))
      (node (ref "LCD1") (pin "P$8") (pinfunction "C1+_P$8") (pintype "bidirectional"))
    )
    (net (code "28") (name "Net-(C17-P$1)") (class "Default")
      (node (ref "C17") (pin "1") (pinfunction "P$1_1") (pintype "passive"))
      (node (ref "LCD1") (pin "P$7") (pinfunction "C2+_P$7") (pintype "bidirectional"))
    )
    (net (code "29") (name "Net-(C17-P$2)") (class "Default")
      (node (ref "C17") (pin "2") (pinfunction "P$2_2") (pintype "passive"))
      (node (ref "LCD1") (pin "P$6") (pinfunction "C2-_P$6") (pintype "bidirectional"))
    )
    (net (code "30") (name "Net-(C18-P$1)") (class "Default")
      (node (ref "C18") (pin "1") (pinfunction "P$1_1") (pintype "passive"))
      (node (ref "LCD1") (pin "P$10") (pinfunction "VOUT_P$10") (pintype "bidirectional"))
    )
    (net (code "31") (name "Net-(CON12-PWR-Pad1-1)") (class "Default")
      (node (ref "CON12") (pin "1-1") (pinfunction "PWR_1-1") (pintype "bidirectional"))
      (node (ref "CON12") (pin "1-2") (pinfunction "PWR_1-2") (pintype "bidirectional"))
      (node (ref "D2") (pin "A") (pinfunction "A_A") (pintype "passive"))
    )
    (net (code "32") (name "Net-(IC2-IN)") (class "Default")
      (node (ref "IC2") (pin "3") (pinfunction "IN_3") (pintype "input"))
      (node (ref "SW3") (pin "3") (pinfunction "3_3") (pintype "bidirectional"))
    )
    (net (code "33") (name "Net-(R11-P$2)") (class "Default")
      (node (ref "LED4") (pin "C") (pinfunction "C_C") (pintype "passive"))
      (node (ref "R11") (pin "2") (pinfunction "P$2_2") (pintype "passive"))
    )
    (net (code "34") (name "Net-(R12-P$2)") (class "Default")
      (node (ref "LED5") (pin "C") (pinfunction "C_C") (pintype "passive"))
      (node (ref "R12") (pin "2") (pinfunction "P$2_2") (pintype "passive"))
    )
    (net (code "35") (name "Net-(R13-P$2)") (class "Default")
      (node (ref "LED6") (pin "C") (pinfunction "C_C") (pintype "passive"))
      (node (ref "R13") (pin "2") (pinfunction "P$2_2") (pintype "passive"))
    )
    (net (code "36") (name "Net-(R17-P$2)") (class "Default")
      (node (ref "LCD1") (pin "A") (pinfunction "A_A") (pintype "bidirectional"))
      (node (ref "R17") (pin "2") (pinfunction "P$2_2") (pintype "passive"))
    )
    (net (code "37") (name "Net-(R19-P$2)") (class "Default")
      (node (ref "R19") (pin "2") (pinfunction "P$2_2") (pintype "passive"))
      (node (ref "R20") (pin "2") (pinfunction "P$2_2") (pintype "passive"))
      (node (ref "R21") (pin "2") (pinfunction "P$2_2") (pintype "passive"))
      (node (ref "TP3") (pin "TP") (pinfunction "TP_TP") (pintype "input"))
    )
    (net (code "38") (name "Net-(R22-P$1)") (class "Default")
      (node (ref "R22") (pin "1") (pinfunction "P$1_1") (pintype "passive"))
      (node (ref "VR1") (pin "P$2") (pinfunction "S_P$2") (pintype "passive"))
    )
    (net (code "39") (name "Net-(R26-P$1)") (class "Default")
      (node (ref "R26") (pin "1") (pinfunction "P$1_1") (pintype "passive"))
      (node (ref "T2") (pin "1") (pinfunction "B_1") (pintype "passive"))
    )
    (net (code "40") (name "Net-(R29-P$2)") (class "Default")
      (node (ref "JP3") (pin "2") (pinfunction "2_2") (pintype "passive"))
      (node (ref "R29") (pin "2") (pinfunction "P$2_2") (pintype "passive"))
      (node (ref "T3") (pin "B") (pinfunction "G_B") (pintype "passive"))
    )
    (net (code "41") (name "Net-(R30-P$2)") (class "Default")
      (node (ref "R30") (pin "2") (pinfunction "P$2_2") (pintype "passive"))
      (node (ref "SW3") (pin "2") (pinfunction "2_2") (pintype "bidirectional"))
      (node (ref "T3") (pin "C") (pinfunction "D_C") (pintype "passive"))
    )
    (net (code "42") (name "PWM0-RED") (class "Default")
      (node (ref "R11") (pin "1") (pinfunction "P$1_1") (pintype "passive"))
      (node (ref "SKT1") (pin "21") (pinfunction "PWM0_21") (pintype "bidirectional"))
      (node (ref "SKT1") (pin "P$61") (pinfunction "P$61_P$61") (pintype "bidirectional"))
    )
    (net (code "43") (name "PWM1-BLUE") (class "Default")
      (node (ref "R12") (pin "1") (pinfunction "P$1_1") (pintype "passive"))
      (node (ref "SKT1") (pin "22") (pinfunction "PWM1_22") (pintype "bidirectional"))
      (node (ref "SKT1") (pin "P$62") (pinfunction "P$62_P$62") (pintype "bidirectional"))
    )
    (net (code "44") (name "PWM2-GREEN") (class "Default")
      (node (ref "R13") (pin "1") (pinfunction "P$1_1") (pintype "passive"))
      (node (ref "SKT1") (pin "23") (pinfunction "PWM2_23") (pintype "bidirectional"))
      (node (ref "SKT1") (pin "P$63") (pinfunction "P$63_P$63") (pintype "bidirectional"))
    )
    (net (code "45") (name "RX1") (class "Default")
      (node (ref "CON2") (pin "1") (pinfunction "RX/SCL_1") (pintype "bidirectional"))
      (node (ref "R23") (pin "2") (pinfunction "P$2_2") (pintype "passive"))
      (node (ref "SKT1") (pin "10") (pinfunction "RX1_10") (pintype "bidirectional"))
      (node (ref "SKT1") (pin "P$50") (pinfunction "P$50_P$50") (pintype "bidirectional"))
    )
    (net (code "46") (name "RX2") (class "Default")
      (node (ref "CON6") (pin "1") (pinfunction "RX/SCL_1") (pintype "bidirectional"))
      (node (ref "R18") (pin "2") (pinfunction "P$2_2") (pintype "passive"))
      (node (ref "SKT1") (pin "31") (pinfunction "RX2_31") (pintype "bidirectional"))
      (node (ref "SKT1") (pin "P$71") (pinfunction "P$71_P$71") (pintype "bidirectional"))
    )
    (net (code "47") (name "SCK1") (class "Default")
      (node (ref "CON1") (pin "1") (pinfunction "SCK_1") (pintype "bidirectional"))
      (node (ref "CON10") (pin "5") (pinfunction "SCK_5") (pintype "bidirectional"))
      (node (ref "LCD1") (pin "P$14") (pinfunction "SCL_P$14") (pintype "bidirectional"))
      (node (ref "SKT1") (pin "15") (pinfunction "SCK1_15") (pintype "bidirectional"))
      (node (ref "SKT1") (pin "P$55") (pinfunction "P$55_P$55") (pintype "bidirectional"))
    )
    (net (code "48") (name "SCK2") (class "Default")
      (node (ref "CON7") (pin "1") (pinfunction "SCK_1") (pintype "bidirectional"))
      (node (ref "SKT1") (pin "26") (pinfunction "SCK2_26") (pintype "bidirectional"))
      (node (ref "SKT1") (pin "P$66") (pinfunction "P$66_P$66") (pintype "bidirectional"))
    )
    (net (code "49") (name "SCL") (class "Default")
      (node (ref "IC4") (pin "2") (pinfunction "SCL_2") (pintype "bidirectional"))
      (node (ref "IC5") (pin "6") (pinfunction "SCL_6") (pintype "bidirectional"))
      (node (ref "JP4") (pin "4") (pinfunction "4_4") (pintype "passive"))
      (node (ref "R15") (pin "1") (pinfunction "P$1_1") (pintype "passive"))
    )
    (net (code "50") (name "SCL1") (class "Default")
      (node (ref "CON5") (pin "1") (pinfunction "RX/SCL_1") (pintype "bidirectional"))
      (node (ref "JP4") (pin "2") (pinfunction "2_2") (pintype "passive"))
      (node (ref "SKT1") (pin "12") (pinfunction "SCL1_12") (pintype "bidirectional"))
      (node (ref "SKT1") (pin "P$52") (pinfunction "P$52_P$52") (pintype "bidirectional"))
    )
    (net (code "51") (name "SCL2") (class "Default")
      (node (ref "CON8") (pin "1") (pinfunction "RX/SCL_1") (pintype "bidirectional"))
      (node (ref "JP4") (pin "6") (pinfunction "6_6") (pintype "passive"))
      (node (ref "SKT1") (pin "29") (pinfunction "SCL2_29") (pintype "bidirectional"))
      (node (ref "SKT1") (pin "P$69") (pinfunction "P$69_P$69") (pintype "bidirectional"))
    )
    (net (code "52") (name "SDA") (class "Default")
      (node (ref "IC4") (pin "1") (pinfunction "SDA_1") (pintype "bidirectional"))
      (node (ref "IC5") (pin "5") (pinfunction "SDA_5") (pintype "bidirectional"))
      (node (ref "JP4") (pin "3") (pinfunction "3_3") (pintype "passive"))
      (node (ref "R14") (pin "1") (pinfunction "P$1_1") (pintype "passive"))
    )
    (net (code "53") (name "SDA1") (class "Default")
      (node (ref "CON5") (pin "2") (pinfunction "TX/SDA_2") (pintype "bidirectional"))
      (node (ref "JP4") (pin "1") (pinfunction "1_1") (pintype "passive"))
      (node (ref "SKT1") (pin "11") (pinfunction "SDA1_11") (pintype "bidirectional"))
      (node (ref "SKT1") (pin "P$51") (pinfunction "P$51_P$51") (pintype "bidirectional"))
    )
    (net (code "54") (name "SDA2") (class "Default")
      (node (ref "CON8") (pin "2") (pinfunction "TX/SDA_2") (pintype "bidirectional"))
      (node (ref "JP4") (pin "5") (pinfunction "5_5") (pintype "passive"))
      (node (ref "SKT1") (pin "30") (pinfunction "SDA2_30") (pintype "bidirectional"))
      (node (ref "SKT1") (pin "P$70") (pinfunction "P$70_P$70") (pintype "bidirectional"))
    )
    (net (code "55") (name "TGT_CTS") (class "Default")
      (node (ref "SKT1") (pin "39") (pinfunction "TGT_CTS_39") (pintype "bidirectional"))
      (node (ref "SKT1") (pin "P$79") (pinfunction "P$79_P$79") (pintype "bidirectional"))
    )
    (net (code "56") (name "TGT_NRESET") (class "Default")
      (node (ref "CON11") (pin "10") (pinfunction "NRESET_10") (pintype "bidirectional"))
      (node (ref "MOD1") (pin "7") (pinfunction "~{RESET}_7") (pintype "bidirectional"))
      (node (ref "SKT1") (pin "6") (pinfunction "NRESET_6") (pintype "bidirectional"))
      (node (ref "SKT1") (pin "P$46") (pinfunction "P$46_P$46") (pintype "bidirectional"))
    )
    (net (code "57") (name "TGT_RTS") (class "Default")
      (node (ref "SKT1") (pin "38") (pinfunction "TGT_RTS_38") (pintype "bidirectional"))
      (node (ref "SKT1") (pin "P$78") (pinfunction "P$78_P$78") (pintype "bidirectional"))
    )
    (net (code "58") (name "TGT_RX") (class "Default")
      (node (ref "CON11") (pin "8") (pinfunction "TGT_RX_8") (pintype "bidirectional"))
      (node (ref "MOD1") (pin "11") (pinfunction "TGT_RX_11") (pintype "bidirectional"))
      (node (ref "SKT1") (pin "8") (pinfunction "TGT_RX_8") (pintype "bidirectional"))
      (node (ref "SKT1") (pin "P$48") (pinfunction "P$48_P$48") (pintype "bidirectional"))
    )
    (net (code "59") (name "TGT_SWCLK") (class "Default")
      (node (ref "CON11") (pin "4") (pinfunction "SWCLK_4") (pintype "bidirectional"))
      (node (ref "MOD1") (pin "3") (pinfunction "SWCLK_3") (pintype "bidirectional"))
      (node (ref "SKT1") (pin "5") (pinfunction "SWCLK_5") (pintype "bidirectional"))
      (node (ref "SKT1") (pin "P$45") (pinfunction "P$45_P$45") (pintype "bidirectional"))
    )
    (net (code "60") (name "TGT_SWDIO") (class "Default")
      (node (ref "CON11") (pin "2") (pinfunction "SWDIO_2") (pintype "bidirectional"))
      (node (ref "MOD1") (pin "5") (pinfunction "SWDIO_5") (pintype "bidirectional"))
      (node (ref "SKT1") (pin "4") (pinfunction "SWDIO_4") (pintype "bidirectional"))
      (node (ref "SKT1") (pin "P$44") (pinfunction "P$44_P$44") (pintype "bidirectional"))
    )
    (net (code "61") (name "TGT_TX") (class "Default")
      (node (ref "CON11") (pin "7") (pinfunction "TGT_TX_7") (pintype "bidirectional"))
      (node (ref "MOD1") (pin "9") (pinfunction "TGT_TX_9") (pintype "bidirectional"))
      (node (ref "SKT1") (pin "7") (pinfunction "TGT_TX_7") (pintype "bidirectional"))
      (node (ref "SKT1") (pin "P$47") (pinfunction "P$47_P$47") (pintype "bidirectional"))
    )
    (net (code "62") (name "TX1") (class "Default")
      (node (ref "CON2") (pin "2") (pinfunction "TX/SDA_2") (pintype "bidirectional"))
      (node (ref "R23") (pin "1") (pinfunction "P$1_1") (pintype "passive"))
      (node (ref "SKT1") (pin "9") (pinfunction "TX1_9") (pintype "bidirectional"))
      (node (ref "SKT1") (pin "P$49") (pinfunction "P$49_P$49") (pintype "bidirectional"))
    )
    (net (code "63") (name "TX2") (class "Default")
      (node (ref "CON6") (pin "2") (pinfunction "TX/SDA_2") (pintype "bidirectional"))
      (node (ref "R18") (pin "1") (pinfunction "P$1_1") (pintype "passive"))
      (node (ref "SKT1") (pin "32") (pinfunction "TX2_32") (pintype "bidirectional"))
      (node (ref "SKT1") (pin "P$72") (pinfunction "P$72_P$72") (pintype "bidirectional"))
    )
    (net (code "64") (name "VCC_GROVE") (class "Default")
      (node (ref "CON2") (pin "3") (pinfunction "VCC_3") (pintype "bidirectional"))
      (node (ref "CON3") (pin "3") (pinfunction "VCC_3") (pintype "bidirectional"))
      (node (ref "CON4") (pin "3") (pinfunction "VCC_3") (pintype "bidirectional"))
      (node (ref "CON5") (pin "3") (pinfunction "VCC_3") (pintype "bidirectional"))
      (node (ref "CON6") (pin "3") (pinfunction "VCC_3") (pintype "bidirectional"))
      (node (ref "CON8") (pin "3") (pinfunction "VCC_3") (pintype "bidirectional"))
      (node (ref "JP1") (pin "2") (pinfunction "2_2") (pintype "passive"))
    )
    (net (code "65") (name "V_ISENSE") (class "Default")
      (node (ref "CON11") (pin "1") (pinfunction "VCC_1") (pintype "bidirectional"))
      (node (ref "R25") (pin "1") (pinfunction "P$1_1") (pintype "passive"))
      (node (ref "SKT1") (pin "2") (pinfunction "3V3_2") (pintype "bidirectional"))
      (node (ref "SKT1") (pin "P$42") (pinfunction "P$42_P$42") (pintype "bidirectional"))
      (node (ref "TP8") (pin "TP") (pinfunction "TP_TP") (pintype "input"))
    )
    (net (code "66") (name "unconnected-(CON10-NC-Pad1)") (class "Default")
      (node (ref "CON10") (pin "1") (pinfunction "NC_1") (pintype "bidirectional"))
    )
    (net (code "67") (name "unconnected-(CON10-NC-Pad8)") (class "Default")
      (node (ref "CON10") (pin "8") (pinfunction "NC_8") (pintype "bidirectional"))
    )
    (net (code "68") (name "unconnected-(CON10-PadCD)") (class "Default")
      (node (ref "CON10") (pin "CD") (pinfunction "CD_CD") (pintype "bidirectional"))
    )
    (net (code "69") (name "unconnected-(CON11-SWO-Pad6)") (class "Default")
      (node (ref "CON11") (pin "6") (pinfunction "SWO_6") (pintype "bidirectional"))
    )
    (net (code "70") (name "unconnected-(CON12-GNDBREAK-Pad2)") (class "Default")
      (node (ref "CON12") (pin "2") (pinfunction "GNDBREAK_2") (pintype "bidirectional"))
    )
    (net (code "71") (name "unconnected-(D3-PadA)") (class "Default")
      (node (ref "D3") (pin "A") (pinfunction "A_A") (pintype "passive"))
    )
    (net (code "72") (name "unconnected-(IC4-OS-Pad3)") (class "Default")
      (node (ref "IC4") (pin "3") (pinfunction "OS_3") (pintype "bidirectional"))
    )
    (net (code "73") (name "unconnected-(IC5-WP-Pad7)") (class "Default")
      (node (ref "IC5") (pin "7") (pinfunction "WP_7") (pintype "bidirectional"))
    )
    (net (code "74") (name "unconnected-(MOD1-IF_GPIO-Pad13)") (class "Default")
      (node (ref "MOD1") (pin "13") (pinfunction "IF_GPIO_13") (pintype "bidirectional"))
    )
    (net (code "75") (name "unconnected-(MOD1-SCL-Pad10)") (class "Default")
      (node (ref "MOD1") (pin "10") (pinfunction "SCL_10") (pintype "bidirectional"))
    )
    (net (code "76") (name "unconnected-(MOD1-SDA-Pad12)") (class "Default")
      (node (ref "MOD1") (pin "12") (pinfunction "SDA_12") (pintype "bidirectional"))
    )
    (net (code "77") (name "unconnected-(MOD1-SWO-Pad4)") (class "Default")
      (node (ref "MOD1") (pin "4") (pinfunction "SWO_4") (pintype "bidirectional"))
    )
    (net (code "78") (name "unconnected-(MOD1-TGT_CTS-Pad8)") (class "Default")
      (node (ref "MOD1") (pin "8") (pinfunction "TGT_CTS_8") (pintype "bidirectional"))
    )
    (net (code "79") (name "unconnected-(MOD1-TGT_RTS-Pad6)") (class "Default")
      (node (ref "MOD1") (pin "6") (pinfunction "TGT_RTS_6") (pintype "bidirectional"))
    )
    (net (code "80") (name "unconnected-(MOD1-VDET-Pad2)") (class "Default")
      (node (ref "MOD1") (pin "2") (pinfunction "VDET_2") (pintype "bidirectional"))
    )
    (net (code "81") (name "unconnected-(SW3-Pad1)") (class "Default")
      (node (ref "SW3") (pin "1") (pinfunction "1_1") (pintype "bidirectional"))
    )
    (net (code "82") (name "unconnected-(SW3-Pad5)") (class "Default")
      (node (ref "SW3") (pin "5") (pinfunction "5_5") (pintype "bidirectional"))
    )
    (net (code "83") (name "unconnected-(SW3-Pad6)") (class "Default")
      (node (ref "SW3") (pin "6") (pinfunction "6_6") (pintype "bidirectional"))
    )
    (net (code "84") (name "unconnected-(SW3-Pad7)") (class "Default")
      (node (ref "SW3") (pin "7") (pinfunction "7_7") (pintype "bidirectional"))
    )
    (net (code "85") (name "~{PWR_OFF}") (class "Default")
      (node (ref "R26") (pin "2") (pinfunction "P$2_2") (pintype "passive"))
      (node (ref "R27") (pin "2") (pinfunction "P$2_2") (pintype "passive"))
    )
  )
)
